# 1_28TFT.net
KiCad netlist of a schematic drawn in EAGLE
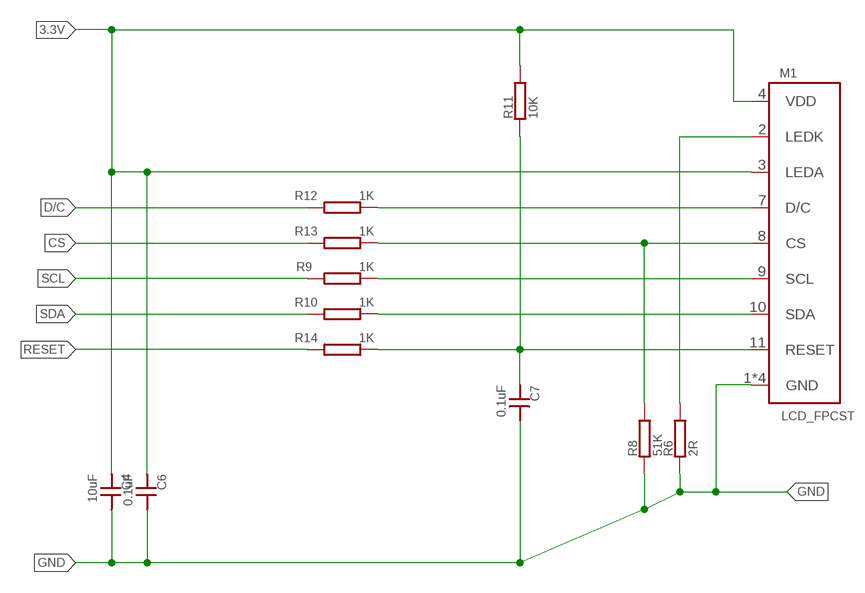
[diagram p0: schematic, sheet 1]

(export (version "E")
  (design (tool "Eeschema 10.0.6"))
  (components
    (comp (ref "C4")
      (value "10uF")
      (footprint "eagle-import:0603")
      (libsource (lib "eagle-import") (part "C0603"))
    )
    (comp (ref "C6")
      (value "0.1uF")
      (footprint "eagle-import:0603")
      (libsource (lib "eagle-import") (part "C0603"))
    )
    (comp (ref "C7")
      (value "0.1uF")
      (footprint "eagle-import:0603")
      (libsource (lib "eagle-import") (part "C0603"))
    )
    (comp (ref "M1")
      (value "LCD_FPCST")
      (footprint "eagle-import:FR-128HR01A")
      (libsource (lib "eagle-import") (part "LCD_FPCST"))
    )
    (comp (ref "R6")
      (value "2R")
      (footprint "eagle-import:0603")
      (libsource (lib "eagle-import") (part "R0603"))
    )
    (comp (ref "R8")
      (value "51K")
      (footprint "eagle-import:0603")
      (libsource (lib "eagle-import") (part "R0603"))
    )
    (comp (ref "R9")
      (value "1K")
      (footprint "eagle-import:0603")
      (libsource (lib "eagle-import") (part "R0603"))
    )
    (comp (ref "R10")
      (value "1K")
      (footprint "eagle-import:0603")
      (libsource (lib "eagle-import") (part "R0603"))
    )
    (comp (ref "R11")
      (value "10K")
      (footprint "eagle-import:0603")
      (libsource (lib "eagle-import") (part "R0603"))
    )
    (comp (ref "R12")
      (value "1K")
      (footprint "eagle-import:0603")
      (libsource (lib "eagle-import") (part "R0603"))
    )
    (comp (ref "R13")
      (value "1K")
      (footprint "eagle-import:0603")
      (libsource (lib "eagle-import") (part "R0603"))
    )
    (comp (ref "R14")
      (value "1K")
      (footprint "eagle-import:0603")
      (libsource (lib "eagle-import") (part "R0603"))
    )
  )
  (nets
    (net (code "1") (name "3.3V") (class "Default")
      (node (ref "C4") (pin "P$1") (pinfunction "P$1_P$1") (pintype "bidirectional"))
      (node (ref "C6") (pin "P$1") (pinfunction "P$1_P$1") (pintype "bidirectional"))
      (node (ref "M1") (pin "3") (pinfunction "LEDA_3") (pintype "bidirectional"))
      (node (ref "M1") (pin "4") (pinfunction "VDD_4") (pintype "bidirectional"))
      (node (ref "R11") (pin "P$2") (pinfunction "P$2_P$2") (pintype "bidirectional"))
    )
    (net (code "2") (name "CS") (class "Default")
      (node (ref "R13") (pin "P$2") (pinfunction "P$2_P$2") (pintype "bidirectional"))
    )
    (net (code "3") (name "D{slash}C") (class "Default")
      (node (ref "R12") (pin "P$2") (pinfunction "P$2_P$2") (pintype "bidirectional"))
    )
    (net (code "4") (name "GND") (class "Default")
      (node (ref "C4") (pin "P$2") (pinfunction "P$2_P$2") (pintype "bidirectional"))
      (node (ref "C6") (pin "P$2") (pinfunction "P$2_P$2") (pintype "bidirectional"))
      (node (ref "C7") (pin "P$2") (pinfunction "P$2_P$2") (pintype "bidirectional"))
      (node (ref "M1") (pin "1") (pinfunction "GND_1") (pintype "bidirectional"))
      (node (ref "M1") (pin "12") (pinfunction "GND_12") (pintype "bidirectional"))
      (node (ref "M1") (pin "5") (pinfunction "GND_5") (pintype "bidirectional"))
      (node (ref "M1") (pin "6") (pinfunction "GND_6") (pintype "bidirectional"))
      (node (ref "R6") (pin "P$1") (pinfunction "P$1_P$1") (pintype "bidirectional"))
      (node (ref "R8") (pin "P$1") (pinfunction "P$1_P$1") (pintype "bidirectional"))
    )
    (net (code "5") (name "Net-(M1-CS)") (class "Default")
      (node (ref "M1") (pin "8") (pinfunction "CS_8") (pintype "bidirectional"))
      (node (ref "R13") (pin "P$1") (pinfunction "P$1_P$1") (pintype "bidirectional"))
      (node (ref "R8") (pin "P$2") (pinfunction "P$2_P$2") (pintype "bidirectional"))
    )
    (net (code "6") (name "Net-(M1-D{slash}C)") (class "Default")
      (node (ref "M1") (pin "7") (pinfunction "D/C_7") (pintype "bidirectional"))
      (node (ref "R12") (pin "P$1") (pinfunction "P$1_P$1") (pintype "bidirectional"))
    )
    (net (code "7") (name "Net-(M1-LEDK)") (class "Default")
      (node (ref "M1") (pin "2") (pinfunction "LEDK_2") (pintype "bidirectional"))
      (node (ref "R6") (pin "P$2") (pinfunction "P$2_P$2") (pintype "bidirectional"))
    )
    (net (code "8") (name "Net-(M1-RESET)") (class "Default")
      (node (ref "C7") (pin "P$1") (pinfunction "P$1_P$1") (pintype "bidirectional"))
      (node (ref "M1") (pin "11") (pinfunction "RESET_11") (pintype "bidirectional"))
      (node (ref "R11") (pin "P$1") (pinfunction "P$1_P$1") (pintype "bidirectional"))
      (node (ref "R14") (pin "P$1") (pinfunction "P$1_P$1") (pintype "bidirectional"))
    )
    (net (code "9") (name "Net-(M1-SCL)") (class "Default")
      (node (ref "M1") (pin "9") (pinfunction "SCL_9") (pintype "bidirectional"))
      (node (ref "R9") (pin "P$1") (pinfunction "P$1_P$1") (pintype "bidirectional"))
    )
    (net (code "10") (name "Net-(M1-SDA)") (class "Default")
      (node (ref "M1") (pin "10") (pinfunction "SDA_10") (pintype "bidirectional"))
      (node (ref "R10") (pin "P$1") (pinfunction "P$1_P$1") (pintype "bidirectional"))
    )
    (net (code "11") (name "RESET") (class "Default")
      (node (ref "R14") (pin "P$2") (pinfunction "P$2_P$2") (pintype "bidirectional"))
    )
    (net (code "12") (name "SCL") (class "Default")
      (node (ref "R9") (pin "P$2") (pinfunction "P$2_P$2") (pintype "bidirectional"))
    )
    (net (code "13") (name "SDA") (class "Default")
      (node (ref "R10") (pin "P$2") (pinfunction "P$2_P$2") (pintype "bidirectional"))
    )
  )
)
